# vibroboard2.net
KiCad netlist of a schematic drawn in EAGLE
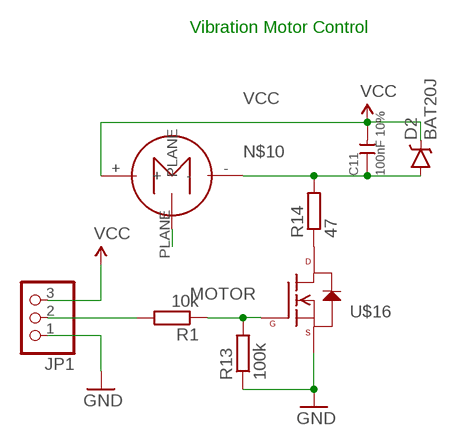
[diagram p0: schematic, sheet 1]

(export (version "E")
  (design (tool "Eeschema 10.0.6"))
  (components
    (comp (ref "C11")
      (value "100nF 10%")
      (footprint "eagle-import:C0603")
      (libsource (lib "eagle-import") (part "CAP-0603"))
    )
    (comp (ref "D2")
      (value "BAT20J")
      (footprint "eagle-import:SOD-323")
      (libsource (lib "eagle-import") (part "DIODE-SCHOTTKY-BAT20J"))
    )
    (comp (ref "JP1")
      (value "PINHD-1X3")
      (footprint "eagle-import:1X03")
      (libsource (lib "eagle-import") (part "PINHD-1X3"))
    )
    (comp (ref "R1")
      (value "10k")
      (footprint "eagle-import:R0603")
      (libsource (lib "eagle-import") (part "R-EU_R0603"))
    )
    (comp (ref "R13")
      (value "100k")
      (footprint "eagle-import:R0603")
      (libsource (lib "eagle-import") (part "R-EU_R0603"))
    )
    (comp (ref "R14")
      (value "47")
      (footprint "eagle-import:R0603")
      (libsource (lib "eagle-import") (part "R-EU_R0603"))
    )
    (comp (ref "U$16")
      (value "N-CHANNEL-MOSFET-BSS138")
      (footprint "eagle-import:SOT23-3")
      (libsource (lib "eagle-import") (part "N-CHANNEL-MOSFET-BSS138"))
    )
    (comp (ref "U$23")
      (value "VIBRO")
      (footprint "eagle-import:VIBRO")
      (libsource (lib "eagle-import") (part "VIBRO"))
    )
  )
  (nets
    (net (code "1") (name "/MOTOR") (class "Default")
      (node (ref "R1") (pin "1") (pinfunction "1_1") (pintype "passive"))
      (node (ref "R13") (pin "2") (pinfunction "2_2") (pintype "passive"))
      (node (ref "U$16") (pin "1") (pinfunction "G_1") (pintype "passive"))
    )
    (net (code "2") (name "/N$10") (class "Default")
      (node (ref "C11") (pin "1") (pinfunction "1_1") (pintype "passive"))
      (node (ref "D2") (pin "A") (pinfunction "A_A") (pintype "passive"))
      (node (ref "R14") (pin "2") (pinfunction "2_2") (pintype "passive"))
      (node (ref "U$23") (pin "-") (pinfunction "-_-") (pintype "bidirectional"))
    )
    (net (code "3") (name "GND") (class "Default")
      (node (ref "JP1") (pin "1") (pinfunction "1_1") (pintype "passive"))
      (node (ref "R13") (pin "1") (pinfunction "1_1") (pintype "passive"))
      (node (ref "U$16") (pin "2") (pinfunction "S_2") (pintype "passive"))
    )
    (net (code "4") (name "Net-(JP1-Pad2)") (class "Default")
      (node (ref "JP1") (pin "2") (pinfunction "2_2") (pintype "passive"))
      (node (ref "R1") (pin "2") (pinfunction "2_2") (pintype "passive"))
    )
    (net (code "5") (name "Net-(U$16-D)") (class "Default")
      (node (ref "R14") (pin "1") (pinfunction "1_1") (pintype "passive"))
      (node (ref "U$16") (pin "3") (pinfunction "D_3") (pintype "passive"))
    )
    (net (code "6") (name "VCC") (class "Default")
      (node (ref "C11") (pin "2") (pinfunction "2_2") (pintype "passive"))
      (node (ref "D2") (pin "C") (pinfunction "C_C") (pintype "passive"))
      (node (ref "JP1") (pin "3") (pinfunction "3_3") (pintype "passive"))
      (node (ref "U$23") (pin "+") (pinfunction "+_+") (pintype "bidirectional"))
    )
    (net (code "7") (name "unconnected-(U$23-PadPLANE)") (class "Default")
      (node (ref "U$23") (pin "PLANE") (pinfunction "PLANE_PLANE") (pintype "bidirectional"))
    )
  )
)
